# BSides_2015_RevA.net
KiCad netlist of a schematic drawn in EAGLE
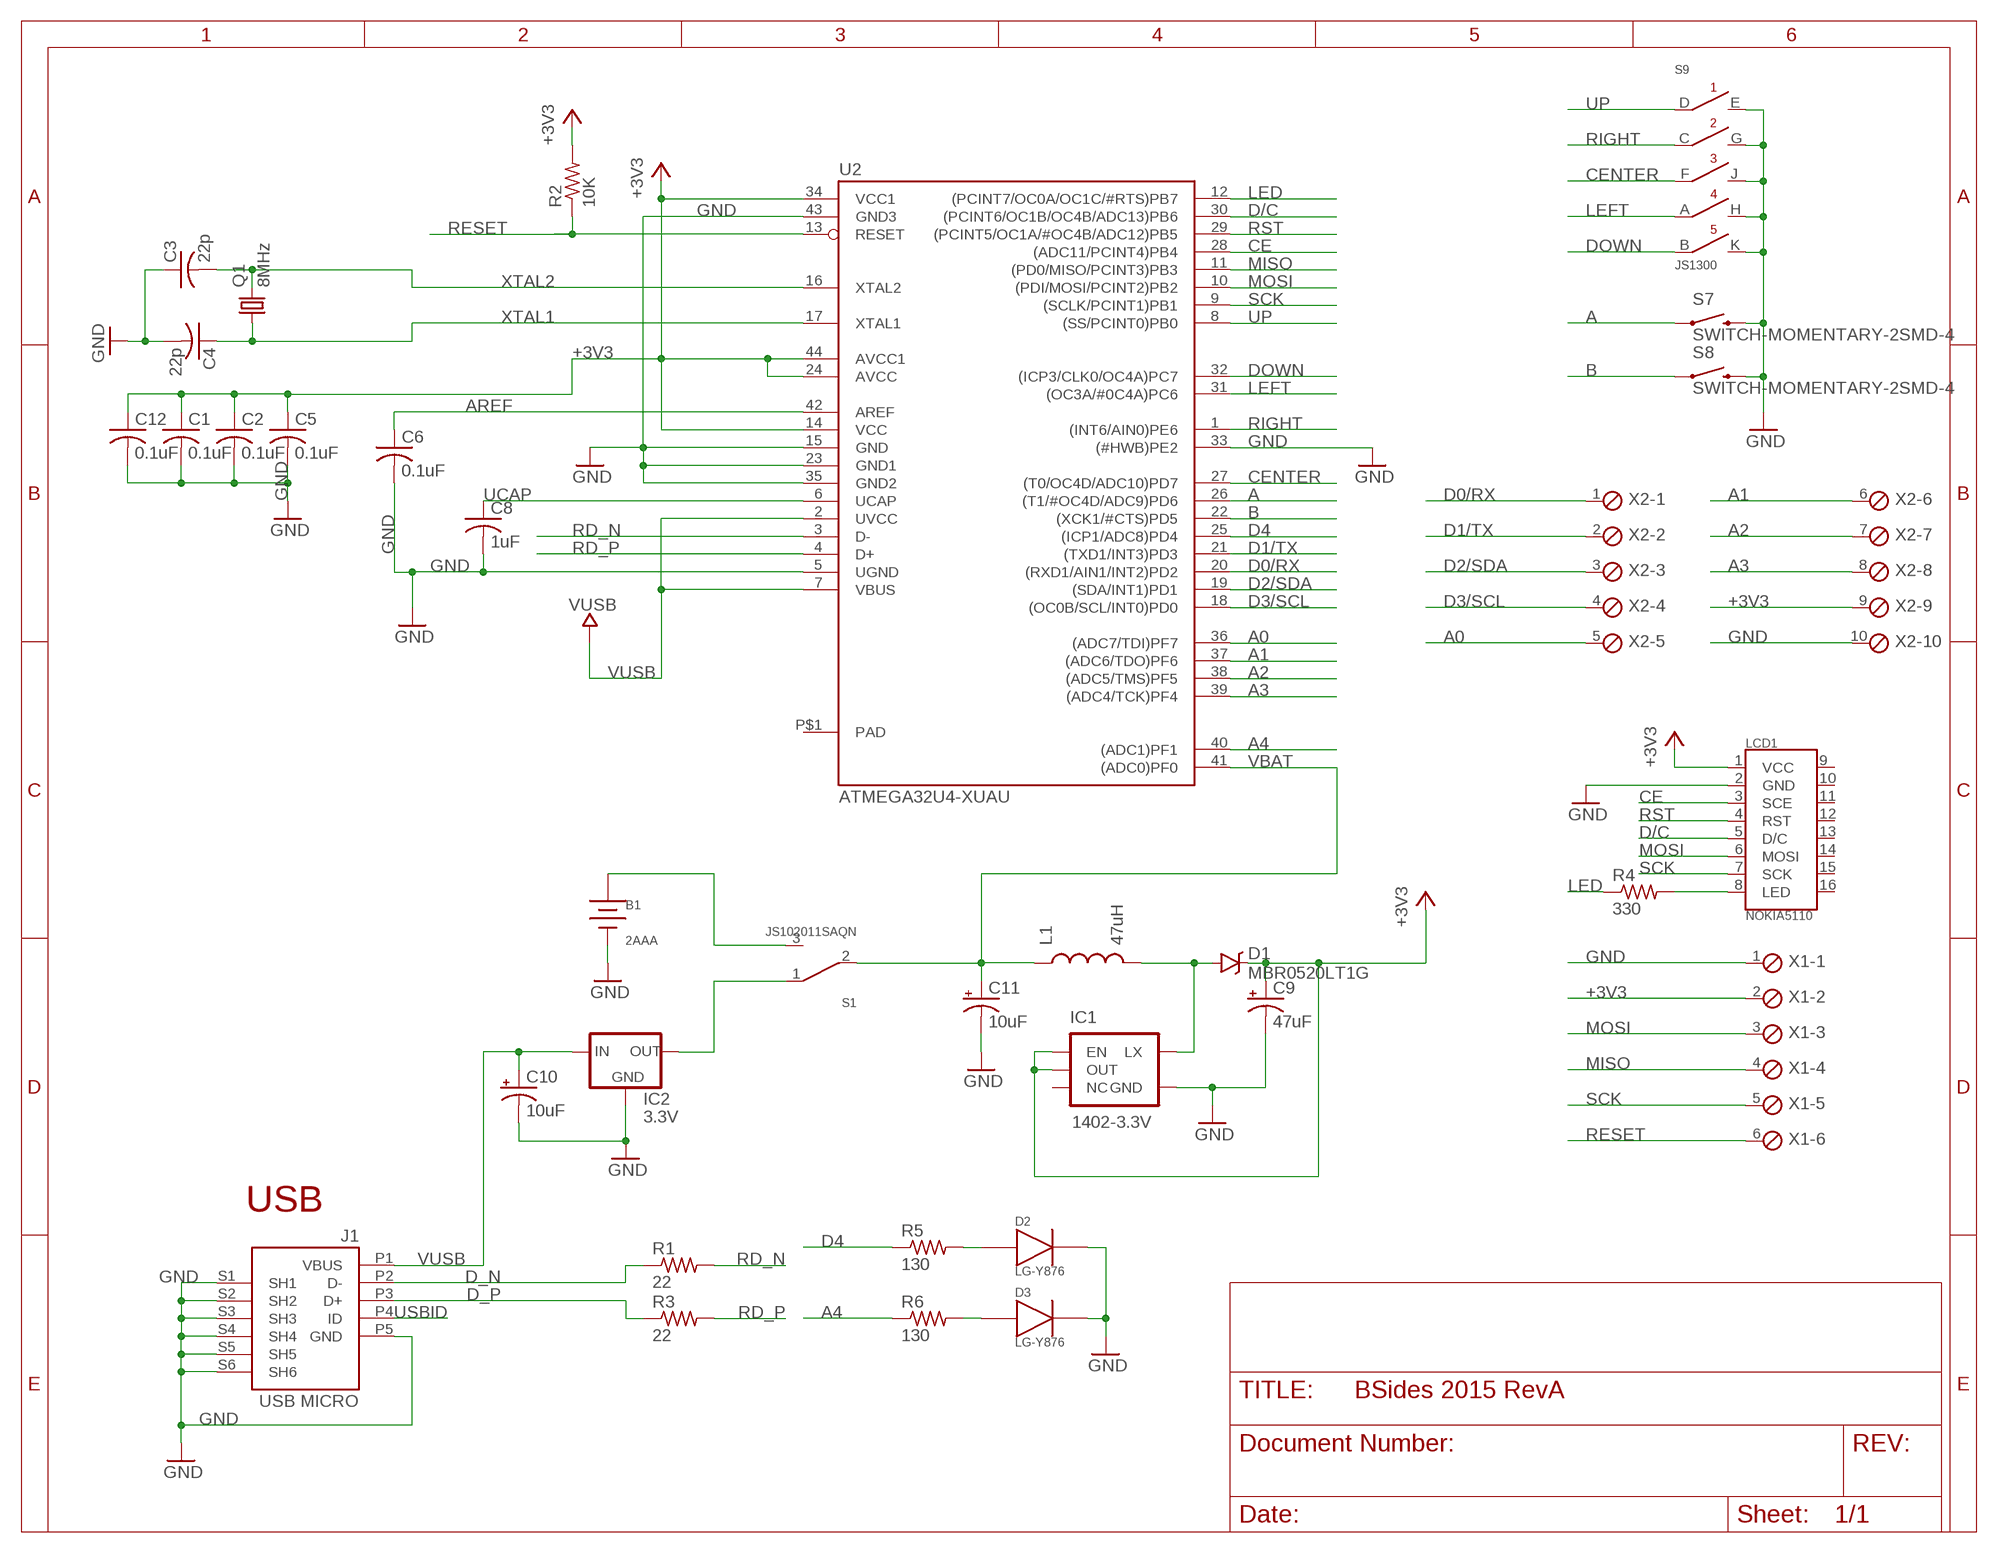
[diagram p0: schematic, sheet 1]

(export (version "E")
  (design (tool "Eeschema 10.0.6"))
  (components
    (comp (ref "B1")
      (value "2AAA")
      (footprint "eagle-import:2AAA")
      (libsource (lib "eagle-import") (part "2AAA"))
    )
    (comp (ref "C1")
      (value "0.1uF")
      (footprint "eagle-import:C0603K")
      (libsource (lib "eagle-import") (part "C-USC0603K"))
    )
    (comp (ref "C2")
      (value "0.1uF")
      (footprint "eagle-import:C0603K")
      (libsource (lib "eagle-import") (part "C-USC0603K"))
    )
    (comp (ref "C3")
      (value "22p")
      (footprint "eagle-import:C0603K")
      (libsource (lib "eagle-import") (part "C-USC0603K"))
    )
    (comp (ref "C4")
      (value "22p")
      (footprint "eagle-import:C0603K")
      (libsource (lib "eagle-import") (part "C-USC0603K"))
    )
    (comp (ref "C5")
      (value "0.1uF")
      (footprint "eagle-import:C0603K")
      (libsource (lib "eagle-import") (part "C-USC0603K"))
    )
    (comp (ref "C6")
      (value "0.1uF")
      (footprint "eagle-import:C0603K")
      (libsource (lib "eagle-import") (part "C-USC0603K"))
    )
    (comp (ref "C8")
      (value "1uF")
      (footprint "eagle-import:C0603K")
      (libsource (lib "eagle-import") (part "C-USC0603K"))
    )
    (comp (ref "C9")
      (value "47uF")
      (footprint "eagle-import:6032")
      (libsource (lib "eagle-import") (part "CAP-TANT"))
    )
    (comp (ref "C10")
      (value "10uF")
      (footprint "eagle-import:EIA3216")
      (libsource (lib "eagle-import") (part "10UF-16V-10%(TANT)"))
    )
    (comp (ref "C11")
      (value "10uF")
      (footprint "eagle-import:EIA3216")
      (libsource (lib "eagle-import") (part "10UF-16V-10%(TANT)"))
    )
    (comp (ref "C12")
      (value "0.1uF")
      (footprint "eagle-import:C0603K")
      (libsource (lib "eagle-import") (part "C-USC0603K"))
    )
    (comp (ref "D1")
      (value "MBR0520LT1G")
      (footprint "eagle-import:SOD-123")
      (libsource (lib "eagle-import") (part "MBR0520LT1G"))
    )
    (comp (ref "D2")
      (value "LG-Y876")
      (footprint "eagle-import:LG-Y876")
      (libsource (lib "eagle-import") (part "LG-Y876"))
    )
    (comp (ref "D3")
      (value "LG-Y876")
      (footprint "eagle-import:LG-Y876")
      (libsource (lib "eagle-import") (part "LG-Y876"))
    )
    (comp (ref "IC1")
      (value "1402-3.3V")
      (footprint "eagle-import:SOT23-5")
      (libsource (lib "eagle-import") (part "V_REG_NCP1400SOT23-5"))
    )
    (comp (ref "IC2")
      (value "3.3V")
      (footprint "eagle-import:SOT23")
      (libsource (lib "eagle-import") (part "XC63FPM"))
    )
    (comp (ref "J1")
      (value "USB MICRO")
      (footprint "eagle-import:CON2_USB_MICRO_B_AT")
      (libsource (lib "eagle-import") (part "MYCON2_USB-MINI-B"))
    )
    (comp (ref "L1")
      (value "47uH")
      (footprint "eagle-import:NR6028")
      (libsource (lib "eagle-import") (part "NR6028"))
    )
    (comp (ref "LCD1")
      (value "NOKIA5110")
      (footprint "eagle-import:5110")
      (libsource (lib "eagle-import") (part "NOKIA5110"))
    )
    (comp (ref "Q1")
      (value "8MHz")
      (footprint "eagle-import:SM49")
      (libsource (lib "eagle-import") (part "CRYSTALSM49"))
    )
    (comp (ref "R1")
      (value "22")
      (footprint "eagle-import:R0603")
      (libsource (lib "eagle-import") (part "R-US_R0603"))
    )
    (comp (ref "R2")
      (value "10K")
      (footprint "eagle-import:R0603")
      (libsource (lib "eagle-import") (part "R-US_R0603"))
    )
    (comp (ref "R3")
      (value "22")
      (footprint "eagle-import:R0603")
      (libsource (lib "eagle-import") (part "R-US_R0603"))
    )
    (comp (ref "R4")
      (value "330")
      (footprint "eagle-import:R0603")
      (libsource (lib "eagle-import") (part "R-US_R0603"))
    )
    (comp (ref "R5")
      (value "130")
      (footprint "eagle-import:R0603")
      (libsource (lib "eagle-import") (part "R-US_R0603"))
    )
    (comp (ref "R6")
      (value "130")
      (footprint "eagle-import:R0603")
      (libsource (lib "eagle-import") (part "R-US_R0603"))
    )
    (comp (ref "S1")
      (value "JS102011SAQN")
      (footprint "eagle-import:SAQN")
      (libsource (lib "eagle-import") (part "JS102011SAQN"))
    )
    (comp (ref "S7")
      (value "SWITCH-MOMENTARY-2SMD-4")
      (footprint "eagle-import:TACTILE_SWITCH_TALL")
      (libsource (lib "eagle-import") (part "SWITCH-MOMENTARY-2SMD-4"))
    )
    (comp (ref "S8")
      (value "SWITCH-MOMENTARY-2SMD-4")
      (footprint "eagle-import:TACTILE_SWITCH_TALL")
      (libsource (lib "eagle-import") (part "SWITCH-MOMENTARY-2SMD-4"))
    )
    (comp (ref "S9")
      (value "JS1300")
      (footprint "eagle-import:JS1300")
      (libsource (lib "eagle-import") (part "JS1300"))
    )
    (comp (ref "U2")
      (value "ATMEGA32U4-XUAU")
      (footprint "eagle-import:TQFP44-PAD")
      (libsource (lib "eagle-import") (part "ATMEGA32U4-XUAU"))
    )
    (comp (ref "X1")
      (value "MPT6")
      (footprint "eagle-import:6POL254")
      (libsource (lib "eagle-import") (part "MPT6"))
    )
    (comp (ref "X2")
      (value "MPT10")
      (footprint "eagle-import:10POL254")
      (libsource (lib "eagle-import") (part "MPT10"))
    )
  )
  (nets
    (net (code "1") (name "+3V3") (class "Default")
      (node (ref "C1") (pin "1") (pinfunction "1_1") (pintype "passive"))
      (node (ref "C12") (pin "1") (pinfunction "1_1") (pintype "passive"))
      (node (ref "C2") (pin "1") (pinfunction "1_1") (pintype "passive"))
      (node (ref "C5") (pin "1") (pinfunction "1_1") (pintype "passive"))
      (node (ref "C9") (pin "P$2") (pinfunction "+_P$2") (pintype "passive"))
      (node (ref "D1") (pin "P$1") (pinfunction "C_P$1") (pintype "passive"))
      (node (ref "IC1") (pin "1") (pinfunction "EN_1") (pintype "input"))
      (node (ref "IC1") (pin "2") (pinfunction "OUT_2") (pintype "passive"))
      (node (ref "LCD1") (pin "1") (pinfunction "VCC_1") (pintype "bidirectional"))
      (node (ref "R2") (pin "2") (pinfunction "2_2") (pintype "passive"))
      (node (ref "U2") (pin "14") (pinfunction "VCC_14") (pintype "power_in"))
      (node (ref "U2") (pin "24") (pinfunction "AVCC_24") (pintype "power_in"))
      (node (ref "U2") (pin "34") (pinfunction "VCC1_34") (pintype "power_in"))
      (node (ref "U2") (pin "44") (pinfunction "AVCC1_44") (pintype "power_in"))
      (node (ref "X1") (pin "2") (pinfunction "1_2") (pintype "passive"))
      (node (ref "X2") (pin "9") (pinfunction "1_9") (pintype "passive"))
    )
    (net (code "2") (name "/A") (class "Default")
      (node (ref "S7") (pin "A2") (pinfunction "1_A2") (pintype "passive"))
      (node (ref "U2") (pin "26") (pinfunction "(T1/#OC4D/ADC9)PD6_26") (pintype "bidirectional"))
    )
    (net (code "3") (name "/A0") (class "Default")
      (node (ref "U2") (pin "36") (pinfunction "(ADC7/TDI)PF7_36") (pintype "bidirectional"))
      (node (ref "X2") (pin "5") (pinfunction "1_5") (pintype "passive"))
    )
    (net (code "4") (name "/A1") (class "Default")
      (node (ref "U2") (pin "37") (pinfunction "(ADC6/TDO)PF6_37") (pintype "bidirectional"))
      (node (ref "X2") (pin "6") (pinfunction "1_6") (pintype "passive"))
    )
    (net (code "5") (name "/A2") (class "Default")
      (node (ref "U2") (pin "38") (pinfunction "(ADC5/TMS)PF5_38") (pintype "bidirectional"))
      (node (ref "X2") (pin "7") (pinfunction "1_7") (pintype "passive"))
    )
    (net (code "6") (name "/A3") (class "Default")
      (node (ref "U2") (pin "39") (pinfunction "(ADC4/TCK)PF4_39") (pintype "bidirectional"))
      (node (ref "X2") (pin "8") (pinfunction "1_8") (pintype "passive"))
    )
    (net (code "7") (name "/A4") (class "Default")
      (node (ref "R6") (pin "1") (pinfunction "1_1") (pintype "passive"))
      (node (ref "U2") (pin "40") (pinfunction "(ADC1)PF1_40") (pintype "bidirectional"))
    )
    (net (code "8") (name "/AREF") (class "Default")
      (node (ref "C6") (pin "1") (pinfunction "1_1") (pintype "passive"))
      (node (ref "U2") (pin "42") (pinfunction "AREF_42") (pintype "power_in"))
    )
    (net (code "9") (name "/B") (class "Default")
      (node (ref "S8") (pin "A2") (pinfunction "1_A2") (pintype "passive"))
      (node (ref "U2") (pin "22") (pinfunction "(XCK1/#CTS)PD5_22") (pintype "bidirectional"))
    )
    (net (code "10") (name "/CE") (class "Default")
      (node (ref "LCD1") (pin "3") (pinfunction "SCE_3") (pintype "bidirectional"))
      (node (ref "U2") (pin "28") (pinfunction "(ADC11/PCINT4)PB4_28") (pintype "bidirectional"))
    )
    (net (code "11") (name "/CENTER") (class "Default")
      (node (ref "S9") (pin "F") (pinfunction "F_F") (pintype "bidirectional"))
      (node (ref "U2") (pin "27") (pinfunction "(T0/OC4D/ADC10)PD7_27") (pintype "bidirectional"))
    )
    (net (code "12") (name "/D0{slash}RX") (class "Default")
      (node (ref "U2") (pin "20") (pinfunction "(RXD1/AIN1/INT2)PD2_20") (pintype "bidirectional"))
      (node (ref "X2") (pin "1") (pinfunction "1_1") (pintype "passive"))
    )
    (net (code "13") (name "/D1{slash}TX") (class "Default")
      (node (ref "U2") (pin "21") (pinfunction "(TXD1/INT3)PD3_21") (pintype "bidirectional"))
      (node (ref "X2") (pin "2") (pinfunction "1_2") (pintype "passive"))
    )
    (net (code "14") (name "/D2{slash}SDA") (class "Default")
      (node (ref "U2") (pin "19") (pinfunction "(SDA/INT1)PD1_19") (pintype "bidirectional"))
      (node (ref "X2") (pin "3") (pinfunction "1_3") (pintype "passive"))
    )
    (net (code "15") (name "/D3{slash}SCL") (class "Default")
      (node (ref "U2") (pin "18") (pinfunction "(OC0B/SCL/INT0)PD0_18") (pintype "bidirectional"))
      (node (ref "X2") (pin "4") (pinfunction "1_4") (pintype "passive"))
    )
    (net (code "16") (name "/D4") (class "Default")
      (node (ref "R5") (pin "1") (pinfunction "1_1") (pintype "passive"))
      (node (ref "U2") (pin "25") (pinfunction "(ICP1/ADC8)PD4_25") (pintype "bidirectional"))
    )
    (net (code "17") (name "/DOWN") (class "Default")
      (node (ref "S9") (pin "B") (pinfunction "B_B") (pintype "bidirectional"))
      (node (ref "U2") (pin "32") (pinfunction "(ICP3/CLK0/OC4A)PC7_32") (pintype "bidirectional"))
    )
    (net (code "18") (name "/D_N") (class "Default")
      (node (ref "J1") (pin "P2") (pinfunction "D-_P2") (pintype "bidirectional"))
      (node (ref "R1") (pin "1") (pinfunction "1_1") (pintype "passive"))
    )
    (net (code "19") (name "/D_P") (class "Default")
      (node (ref "J1") (pin "P3") (pinfunction "D+_P3") (pintype "bidirectional"))
      (node (ref "R3") (pin "1") (pinfunction "1_1") (pintype "passive"))
    )
    (net (code "20") (name "/D{slash}C") (class "Default")
      (node (ref "LCD1") (pin "5") (pinfunction "D/C_5") (pintype "bidirectional"))
      (node (ref "U2") (pin "30") (pinfunction "(PCINT6/OC1B/OC4B/ADC13)PB6_30") (pintype "bidirectional"))
    )
    (net (code "21") (name "/LED") (class "Default")
      (node (ref "R4") (pin "1") (pinfunction "1_1") (pintype "passive"))
      (node (ref "U2") (pin "12") (pinfunction "(PCINT7/OC0A/OC1C/#RTS)PB7_12") (pintype "bidirectional"))
    )
    (net (code "22") (name "/LEFT") (class "Default")
      (node (ref "S9") (pin "A") (pinfunction "A_A") (pintype "bidirectional"))
      (node (ref "U2") (pin "31") (pinfunction "(OC3A/#0C4A)PC6_31") (pintype "bidirectional"))
    )
    (net (code "23") (name "/MISO") (class "Default")
      (node (ref "U2") (pin "11") (pinfunction "(PD0/MISO/PCINT3)PB3_11") (pintype "bidirectional"))
      (node (ref "X1") (pin "4") (pinfunction "1_4") (pintype "passive"))
    )
    (net (code "24") (name "/MOSI") (class "Default")
      (node (ref "LCD1") (pin "6") (pinfunction "MOSI_6") (pintype "bidirectional"))
      (node (ref "U2") (pin "10") (pinfunction "(PDI/MOSI/PCINT2)PB2_10") (pintype "bidirectional"))
      (node (ref "X1") (pin "3") (pinfunction "1_3") (pintype "passive"))
    )
    (net (code "25") (name "/PAD") (class "Default")
      (node (ref "U2") (pin "P$1") (pinfunction "PAD_P$1") (pintype "power_in"))
    )
    (net (code "26") (name "/RD_N") (class "Default")
      (node (ref "R1") (pin "2") (pinfunction "2_2") (pintype "passive"))
      (node (ref "U2") (pin "3") (pinfunction "D-_3") (pintype "bidirectional"))
    )
    (net (code "27") (name "/RD_P") (class "Default")
      (node (ref "R3") (pin "2") (pinfunction "2_2") (pintype "passive"))
      (node (ref "U2") (pin "4") (pinfunction "D+_4") (pintype "bidirectional"))
    )
    (net (code "28") (name "/RESET") (class "Default")
      (node (ref "R2") (pin "1") (pinfunction "1_1") (pintype "passive"))
      (node (ref "U2") (pin "13") (pinfunction "RESET_13") (pintype "input"))
      (node (ref "X1") (pin "6") (pinfunction "1_6") (pintype "passive"))
    )
    (net (code "29") (name "/RIGHT") (class "Default")
      (node (ref "S9") (pin "C") (pinfunction "C_C") (pintype "bidirectional"))
      (node (ref "U2") (pin "1") (pinfunction "(INT6/AIN0)PE6_1") (pintype "bidirectional"))
    )
    (net (code "30") (name "/RST") (class "Default")
      (node (ref "LCD1") (pin "4") (pinfunction "RST_4") (pintype "bidirectional"))
      (node (ref "U2") (pin "29") (pinfunction "(PCINT5/OC1A/#OC4B/ADC12)PB5_29") (pintype "bidirectional"))
    )
    (net (code "31") (name "/SCK") (class "Default")
      (node (ref "LCD1") (pin "7") (pinfunction "SCK_7") (pintype "bidirectional"))
      (node (ref "U2") (pin "9") (pinfunction "(SCLK/PCINT1)PB1_9") (pintype "bidirectional"))
      (node (ref "X1") (pin "5") (pinfunction "1_5") (pintype "passive"))
    )
    (net (code "32") (name "/UCAP") (class "Default")
      (node (ref "C8") (pin "1") (pinfunction "1_1") (pintype "passive"))
      (node (ref "U2") (pin "6") (pinfunction "UCAP_6") (pintype "passive"))
    )
    (net (code "33") (name "/UP") (class "Default")
      (node (ref "S9") (pin "D") (pinfunction "D_D") (pintype "bidirectional"))
      (node (ref "U2") (pin "8") (pinfunction "(SS/PCINT0)PB0_8") (pintype "bidirectional"))
    )
    (net (code "34") (name "/USBID") (class "Default")
      (node (ref "J1") (pin "P4") (pinfunction "ID_P4") (pintype "bidirectional"))
    )
    (net (code "35") (name "/VBAT") (class "Default")
      (node (ref "C11") (pin "A") (pinfunction "+_A") (pintype "passive"))
      (node (ref "L1") (pin "P$1") (pinfunction "1_P$1") (pintype "passive"))
      (node (ref "S1") (pin "2") (pinfunction "P2_2") (pintype "bidirectional"))
      (node (ref "U2") (pin "41") (pinfunction "(ADC0)PF0_41") (pintype "bidirectional"))
    )
    (net (code "36") (name "/XTAL1") (class "Default")
      (node (ref "C4") (pin "1") (pinfunction "1_1") (pintype "passive"))
      (node (ref "Q1") (pin "1") (pinfunction "1_1") (pintype "passive"))
      (node (ref "U2") (pin "17") (pinfunction "XTAL1_17") (pintype "bidirectional"))
    )
    (net (code "37") (name "/XTAL2") (class "Default")
      (node (ref "C3") (pin "2") (pinfunction "2_2") (pintype "passive"))
      (node (ref "Q1") (pin "2") (pinfunction "2_2") (pintype "passive"))
      (node (ref "U2") (pin "16") (pinfunction "XTAL2_16") (pintype "bidirectional"))
    )
    (net (code "38") (name "GND") (class "Default")
      (node (ref "B1") (pin "-") (pinfunction "-_-") (pintype "bidirectional"))
      (node (ref "C1") (pin "2") (pinfunction "2_2") (pintype "passive"))
      (node (ref "C10") (pin "C") (pinfunction "-_C") (pintype "passive"))
      (node (ref "C11") (pin "C") (pinfunction "-_C") (pintype "passive"))
      (node (ref "C12") (pin "2") (pinfunction "2_2") (pintype "passive"))
      (node (ref "C2") (pin "2") (pinfunction "2_2") (pintype "passive"))
      (node (ref "C3") (pin "1") (pinfunction "1_1") (pintype "passive"))
      (node (ref "C4") (pin "2") (pinfunction "2_2") (pintype "passive"))
      (node (ref "C5") (pin "2") (pinfunction "2_2") (pintype "passive"))
      (node (ref "C6") (pin "2") (pinfunction "2_2") (pintype "passive"))
      (node (ref "C8") (pin "2") (pinfunction "2_2") (pintype "passive"))
      (node (ref "C9") (pin "P$1") (pinfunction "-_P$1") (pintype "passive"))
      (node (ref "D2") (pin "C") (pinfunction "C_C") (pintype "bidirectional"))
      (node (ref "D3") (pin "C") (pinfunction "C_C") (pintype "bidirectional"))
      (node (ref "IC1") (pin "4") (pinfunction "GND_4") (pintype "input"))
      (node (ref "IC2") (pin "1") (pinfunction "GND_1") (pintype "input"))
      (node (ref "J1") (pin "P5") (pinfunction "GND_P5") (pintype "passive"))
      (node (ref "J1") (pin "S1") (pinfunction "SH1_S1") (pintype "passive"))
      (node (ref "J1") (pin "S2") (pinfunction "SH2_S2") (pintype "passive"))
      (node (ref "J1") (pin "S3") (pinfunction "SH3_S3") (pintype "passive"))
      (node (ref "J1") (pin "S4") (pinfunction "SH4_S4") (pintype "passive"))
      (node (ref "J1") (pin "S5") (pinfunction "SH5_S5") (pintype "passive"))
      (node (ref "J1") (pin "S6") (pinfunction "SH6_S6") (pintype "passive"))
      (node (ref "LCD1") (pin "2") (pinfunction "GND_2") (pintype "bidirectional"))
      (node (ref "S7") (pin "B2") (pinfunction "2_B2") (pintype "passive"))
      (node (ref "S8") (pin "B2") (pinfunction "2_B2") (pintype "passive"))
      (node (ref "S9") (pin "E") (pinfunction "E_E") (pintype "bidirectional"))
      (node (ref "S9") (pin "G") (pinfunction "G_G") (pintype "bidirectional"))
      (node (ref "S9") (pin "H") (pinfunction "H_H") (pintype "bidirectional"))
      (node (ref "S9") (pin "J") (pinfunction "J_J") (pintype "bidirectional"))
      (node (ref "S9") (pin "K") (pinfunction "K_K") (pintype "bidirectional"))
      (node (ref "U2") (pin "15") (pinfunction "GND_15") (pintype "power_in"))
      (node (ref "U2") (pin "23") (pinfunction "GND1_23") (pintype "power_in"))
      (node (ref "U2") (pin "33") (pinfunction "(#HWB)PE2_33") (pintype "bidirectional"))
      (node (ref "U2") (pin "35") (pinfunction "GND2_35") (pintype "power_in"))
      (node (ref "U2") (pin "43") (pinfunction "GND3_43") (pintype "power_in"))
      (node (ref "U2") (pin "5") (pinfunction "UGND_5") (pintype "power_in"))
      (node (ref "X1") (pin "1") (pinfunction "1_1") (pintype "passive"))
      (node (ref "X2") (pin "10") (pinfunction "1_10") (pintype "passive"))
    )
    (net (code "39") (name "Net-(D1-A)") (class "Default")
      (node (ref "D1") (pin "P$2") (pinfunction "A_P$2") (pintype "passive"))
      (node (ref "IC1") (pin "5") (pinfunction "LX_5") (pintype "input"))
      (node (ref "L1") (pin "P$2") (pinfunction "2_P$2") (pintype "passive"))
    )
    (net (code "40") (name "Net-(D2-PadA)") (class "Default")
      (node (ref "D2") (pin "A") (pinfunction "A_A") (pintype "bidirectional"))
      (node (ref "R5") (pin "2") (pinfunction "2_2") (pintype "passive"))
    )
    (net (code "41") (name "Net-(D3-PadA)") (class "Default")
      (node (ref "D3") (pin "A") (pinfunction "A_A") (pintype "bidirectional"))
      (node (ref "R6") (pin "2") (pinfunction "2_2") (pintype "passive"))
    )
    (net (code "42") (name "Net-(IC2-OUT)") (class "Default")
      (node (ref "IC2") (pin "2") (pinfunction "OUT_2") (pintype "passive"))
      (node (ref "S1") (pin "1") (pinfunction "P1_1") (pintype "bidirectional"))
    )
    (net (code "43") (name "Net-(LCD1-LED)") (class "Default")
      (node (ref "LCD1") (pin "8") (pinfunction "LED_8") (pintype "bidirectional"))
      (node (ref "R4") (pin "2") (pinfunction "2_2") (pintype "passive"))
    )
    (net (code "44") (name "Net-(S1-P3)") (class "Default")
      (node (ref "B1") (pin "+") (pinfunction "+_+") (pintype "bidirectional"))
      (node (ref "S1") (pin "3") (pinfunction "P3_3") (pintype "bidirectional"))
    )
    (net (code "45") (name "VUSB") (class "Default")
      (node (ref "C10") (pin "A") (pinfunction "+_A") (pintype "passive"))
      (node (ref "IC2") (pin "3") (pinfunction "IN_3") (pintype "input"))
      (node (ref "J1") (pin "P1") (pinfunction "VBUS_P1") (pintype "power_in"))
      (node (ref "U2") (pin "2") (pinfunction "UVCC_2") (pintype "power_in"))
      (node (ref "U2") (pin "7") (pinfunction "VBUS_7") (pintype "input"))
    )
    (net (code "46") (name "unconnected-(IC1-NC-Pad3)") (class "Default")
      (node (ref "IC1") (pin "3") (pinfunction "NC_3") (pintype "input"))
    )
    (net (code "47") (name "unconnected-(LCD1-P$9-Pad9)") (class "Default")
      (node (ref "LCD1") (pin "9") (pinfunction "P$9_9") (pintype "bidirectional"))
    )
    (net (code "48") (name "unconnected-(LCD1-P$10-Pad10)") (class "Default")
      (node (ref "LCD1") (pin "10") (pinfunction "P$10_10") (pintype "bidirectional"))
    )
    (net (code "49") (name "unconnected-(LCD1-P$11-Pad11)") (class "Default")
      (node (ref "LCD1") (pin "11") (pinfunction "P$11_11") (pintype "bidirectional"))
    )
    (net (code "50") (name "unconnected-(LCD1-P$12-Pad12)") (class "Default")
      (node (ref "LCD1") (pin "12") (pinfunction "P$12_12") (pintype "bidirectional"))
    )
    (net (code "51") (name "unconnected-(LCD1-P$13-Pad13)") (class "Default")
      (node (ref "LCD1") (pin "13") (pinfunction "P$13_13") (pintype "bidirectional"))
    )
    (net (code "52") (name "unconnected-(LCD1-P$14-Pad14)") (class "Default")
      (node (ref "LCD1") (pin "14") (pinfunction "P$14_14") (pintype "bidirectional"))
    )
    (net (code "53") (name "unconnected-(LCD1-P$15-Pad15)") (class "Default")
      (node (ref "LCD1") (pin "15") (pinfunction "P$15_15") (pintype "bidirectional"))
    )
    (net (code "54") (name "unconnected-(LCD1-P$16-Pad16)") (class "Default")
      (node (ref "LCD1") (pin "16") (pinfunction "P$16_16") (pintype "bidirectional"))
    )
  )
)
